# ESP32Programmer.net
KiCad netlist of a schematic drawn in Altium Designer
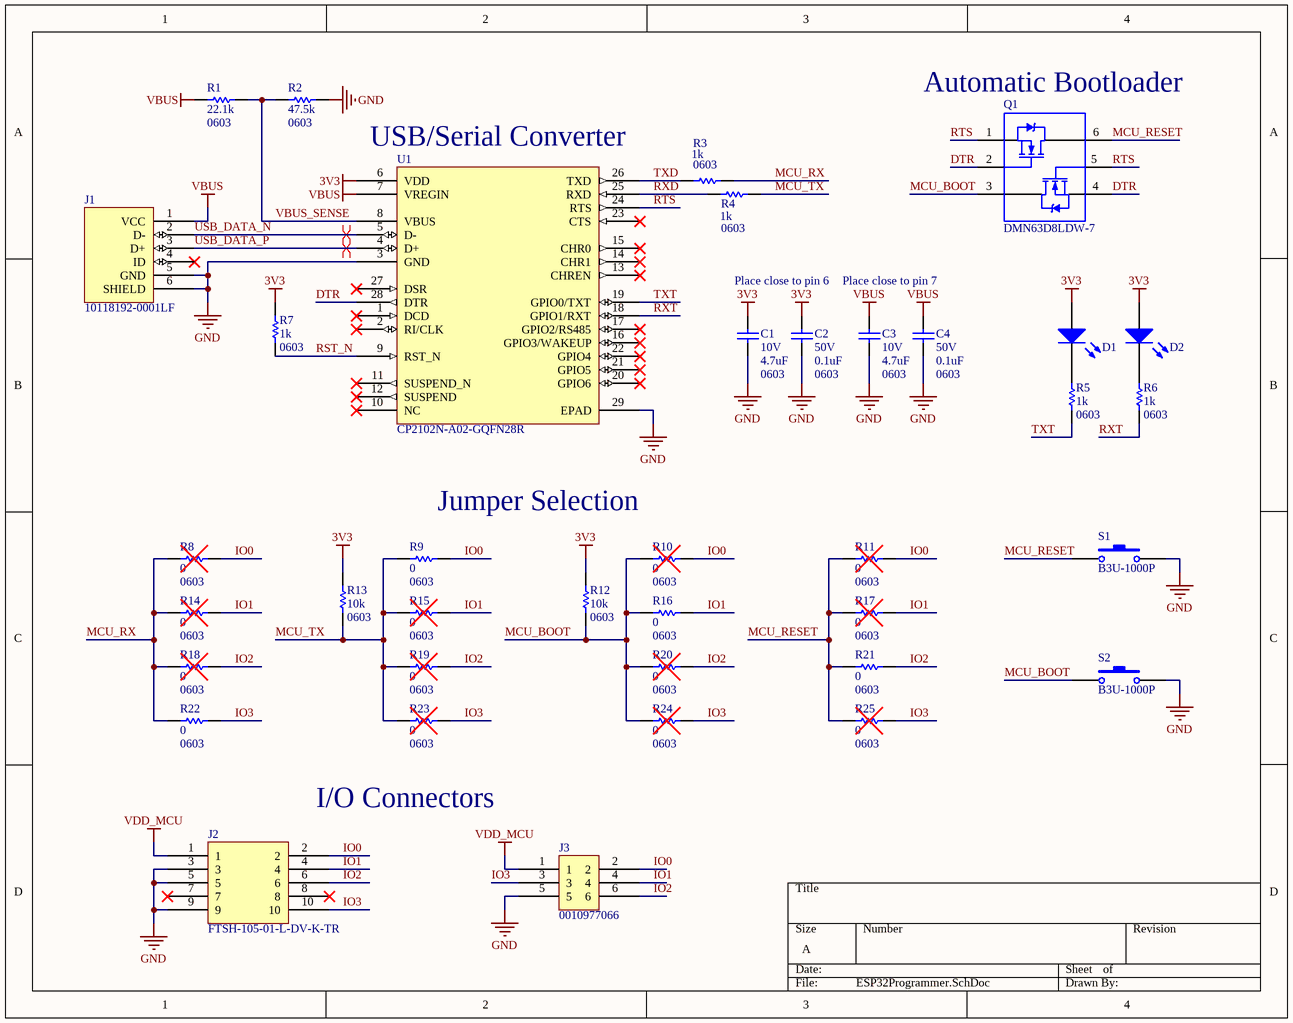
[diagram p0: ESP32Programmer.SchDoc]

(export (version "E")
  (design (tool "Eeschema 10.0.6"))
  (components
    (comp (ref "C1")
      (value "4.7uF")
      (footprint "Footprint_Capacitor:CAPC1608X09N")
      (description "General purpose capacitor")
      (fields
        (field (name "RATED VOLTAGE") "10V")
        (field (name "PACKAGE") "0603")
        (field (name "Comment") "Capacitor")
      )
      (libsource (lib "Schematic_Generic") (part "Capacitor"))
    )
    (comp (ref "C2")
      (value "0.1uF")
      (footprint "Footprint_Capacitor:CAPC1608X09N")
      (description "General purpose capacitor")
      (fields
        (field (name "RATED VOLTAGE") "50V")
        (field (name "PACKAGE") "0603")
        (field (name "Comment") "Capacitor")
      )
      (libsource (lib "Schematic_Generic") (part "Capacitor"))
    )
    (comp (ref "C3")
      (value "4.7uF")
      (footprint "Footprint_Capacitor:CAPC1608X09N")
      (description "General purpose capacitor")
      (fields
        (field (name "RATED VOLTAGE") "10V")
        (field (name "PACKAGE") "0603")
        (field (name "Comment") "Capacitor")
      )
      (libsource (lib "Schematic_Generic") (part "Capacitor"))
    )
    (comp (ref "C4")
      (value "0.1uF")
      (footprint "Footprint_Capacitor:CAPC1608X09N")
      (description "General purpose capacitor")
      (fields
        (field (name "RATED VOLTAGE") "50V")
        (field (name "PACKAGE") "0603")
        (field (name "Comment") "Capacitor")
      )
      (libsource (lib "Schematic_Generic") (part "Capacitor"))
    )
    (comp (ref "D1")
      (value "LED")
      (footprint "Footprint_LED:DIOC1608X09N")
      (description "General purpose LED")
      (libsource (lib "Schematic_Generic") (part "LED"))
    )
    (comp (ref "D2")
      (value "LED")
      (footprint "Footprint_LED:DIOC1608X09N")
      (description "General purpose LED")
      (libsource (lib "Schematic_Generic") (part "LED"))
    )
    (comp (ref "J1")
      (value "10118192-0001LF")
      (footprint "Footprint_Connector:10118192-0001LF")
      (description "Conn Micro USB 2.0 Type B RCP 5 POS 0.65mm Solder RA SMD 5 Terminal 1 Port T/R")
      (fields (field (name "MANUFACTURER") "Framatome Connectors"))
      (libsource (lib "Schematic_Connector") (part "10118192-0001LF"))
    )
    (comp (ref "J2")
      (value "FTSH-105-01-L-DV-K-TR")
      (footprint "Footprint_Connector:FTSH-105-01-L-DV-K-TR")
      (description "SAMTEC - FTSH-105-01-L-DV-K-TR - CONNECTOR, HEADER, 10 POSITION, 2ROW, 1.27MM")
      (fields (field (name "MANUFACTURER") "Samtec"))
      (libsource (lib "Schematic_Connector") (part "FTSH-105-01-L-DV-K-TR"))
    )
    (comp (ref "J3")
      (value "0010977066")
      (footprint "Footprint_Connector:3X2 MALE HEADER")
      (description "Conn Unshrouded Header HDR 6 POS 2.54mm Solder ST Thru-Hole C-GridR Bag")
      (fields (field (name "MANUFACTURER") "Molex"))
      (libsource (lib "Schematic_Connector") (part "0010977066"))
    )
    (comp (ref "Q1")
      (value "DMN63D8LDW-7")
      (footprint "Footprint_Transistor:SOT65P210X110-6N")
      (description "DIODES INC. - DMN63D8LDW-7 - Dual MOSFET, N Channel, 30 V, 260 mA, 2.8 ohm, SOT-363, Surface Mount")
      (fields (field (name "MANUFACTURER") "Diodes"))
      (libsource (lib "Schematic_Transistor") (part "DMN63D8LDW-7"))
    )
    (comp (ref "R1")
      (value "22.1k")
      (footprint "Footprint_Resistor:RESC1608X06N")
      (description "General purpose resistor")
      (fields (field (name "PACKAGE") "0603") (field (name "Comment") "Resistor"))
      (libsource (lib "Schematic_Generic") (part "Resistor"))
    )
    (comp (ref "R2")
      (value "47.5k")
      (footprint "Footprint_Resistor:RESC1608X06N")
      (description "General purpose resistor")
      (fields (field (name "PACKAGE") "0603") (field (name "Comment") "Resistor"))
      (libsource (lib "Schematic_Generic") (part "Resistor"))
    )
    (comp (ref "R3")
      (value "1k")
      (footprint "Footprint_Resistor:RESC1608X06N")
      (description "General purpose resistor")
      (fields (field (name "PACKAGE") "0603") (field (name "Comment") "Resistor"))
      (libsource (lib "Schematic_Generic") (part "Resistor"))
    )
    (comp (ref "R4")
      (value "1k")
      (footprint "Footprint_Resistor:RESC1608X06N")
      (description "General purpose resistor")
      (fields (field (name "PACKAGE") "0603") (field (name "Comment") "Resistor"))
      (libsource (lib "Schematic_Generic") (part "Resistor"))
    )
    (comp (ref "R5")
      (value "1k")
      (footprint "Footprint_Resistor:RESC1608X06N")
      (description "General purpose resistor")
      (fields (field (name "PACKAGE") "0603") (field (name "Comment") "Resistor"))
      (libsource (lib "Schematic_Generic") (part "Resistor"))
    )
    (comp (ref "R6")
      (value "1k")
      (footprint "Footprint_Resistor:RESC1608X06N")
      (description "General purpose resistor")
      (fields (field (name "PACKAGE") "0603") (field (name "Comment") "Resistor"))
      (libsource (lib "Schematic_Generic") (part "Resistor"))
    )
    (comp (ref "R7")
      (value "1k")
      (footprint "Footprint_Resistor:RESC1608X06N")
      (description "General purpose resistor")
      (fields (field (name "PACKAGE") "0603") (field (name "Comment") "Resistor"))
      (libsource (lib "Schematic_Generic") (part "Resistor"))
    )
    (comp (ref "R8")
      (value "0")
      (footprint "Footprint_Resistor:RESC1608X06N")
      (description "General purpose resistor")
      (fields (field (name "PACKAGE") "0603") (field (name "Comment") "Resistor"))
      (libsource (lib "Schematic_Generic") (part "Resistor"))
    )
    (comp (ref "R9")
      (value "0")
      (footprint "Footprint_Resistor:RESC1608X06N")
      (description "General purpose resistor")
      (fields (field (name "PACKAGE") "0603") (field (name "Comment") "Resistor"))
      (libsource (lib "Schematic_Generic") (part "Resistor"))
    )
    (comp (ref "R10")
      (value "0")
      (footprint "Footprint_Resistor:RESC1608X06N")
      (description "General purpose resistor")
      (fields (field (name "PACKAGE") "0603") (field (name "Comment") "Resistor"))
      (libsource (lib "Schematic_Generic") (part "Resistor"))
    )
    (comp (ref "R11")
      (value "0")
      (footprint "Footprint_Resistor:RESC1608X06N")
      (description "General purpose resistor")
      (fields (field (name "PACKAGE") "0603") (field (name "Comment") "Resistor"))
      (libsource (lib "Schematic_Generic") (part "Resistor"))
    )
    (comp (ref "R12")
      (value "10k")
      (footprint "Footprint_Resistor:RESC1608X06N")
      (description "General purpose resistor")
      (fields (field (name "PACKAGE") "0603") (field (name "Comment") "Resistor"))
      (libsource (lib "Schematic_Generic") (part "Resistor"))
    )
    (comp (ref "R13")
      (value "10k")
      (footprint "Footprint_Resistor:RESC1608X06N")
      (description "General purpose resistor")
      (fields (field (name "PACKAGE") "0603") (field (name "Comment") "Resistor"))
      (libsource (lib "Schematic_Generic") (part "Resistor"))
    )
    (comp (ref "R14")
      (value "0")
      (footprint "Footprint_Resistor:RESC1608X06N")
      (description "General purpose resistor")
      (fields (field (name "PACKAGE") "0603") (field (name "Comment") "Resistor"))
      (libsource (lib "Schematic_Generic") (part "Resistor"))
    )
    (comp (ref "R15")
      (value "0")
      (footprint "Footprint_Resistor:RESC1608X06N")
      (description "General purpose resistor")
      (fields (field (name "PACKAGE") "0603") (field (name "Comment") "Resistor"))
      (libsource (lib "Schematic_Generic") (part "Resistor"))
    )
    (comp (ref "R16")
      (value "0")
      (footprint "Footprint_Resistor:RESC1608X06N")
      (description "General purpose resistor")
      (fields (field (name "PACKAGE") "0603") (field (name "Comment") "Resistor"))
      (libsource (lib "Schematic_Generic") (part "Resistor"))
    )
    (comp (ref "R17")
      (value "0")
      (footprint "Footprint_Resistor:RESC1608X06N")
      (description "General purpose resistor")
      (fields (field (name "PACKAGE") "0603") (field (name "Comment") "Resistor"))
      (libsource (lib "Schematic_Generic") (part "Resistor"))
    )
    (comp (ref "R18")
      (value "0")
      (footprint "Footprint_Resistor:RESC1608X06N")
      (description "General purpose resistor")
      (fields (field (name "PACKAGE") "0603") (field (name "Comment") "Resistor"))
      (libsource (lib "Schematic_Generic") (part "Resistor"))
    )
    (comp (ref "R19")
      (value "0")
      (footprint "Footprint_Resistor:RESC1608X06N")
      (description "General purpose resistor")
      (fields (field (name "PACKAGE") "0603") (field (name "Comment") "Resistor"))
      (libsource (lib "Schematic_Generic") (part "Resistor"))
    )
    (comp (ref "R20")
      (value "0")
      (footprint "Footprint_Resistor:RESC1608X06N")
      (description "General purpose resistor")
      (fields (field (name "PACKAGE") "0603") (field (name "Comment") "Resistor"))
      (libsource (lib "Schematic_Generic") (part "Resistor"))
    )
    (comp (ref "R21")
      (value "0")
      (footprint "Footprint_Resistor:RESC1608X06N")
      (description "General purpose resistor")
      (fields (field (name "PACKAGE") "0603") (field (name "Comment") "Resistor"))
      (libsource (lib "Schematic_Generic") (part "Resistor"))
    )
    (comp (ref "R22")
      (value "0")
      (footprint "Footprint_Resistor:RESC1608X06N")
      (description "General purpose resistor")
      (fields (field (name "PACKAGE") "0603") (field (name "Comment") "Resistor"))
      (libsource (lib "Schematic_Generic") (part "Resistor"))
    )
    (comp (ref "R23")
      (value "0")
      (footprint "Footprint_Resistor:RESC1608X06N")
      (description "General purpose resistor")
      (fields (field (name "PACKAGE") "0603") (field (name "Comment") "Resistor"))
      (libsource (lib "Schematic_Generic") (part "Resistor"))
    )
    (comp (ref "R24")
      (value "0")
      (footprint "Footprint_Resistor:RESC1608X06N")
      (description "General purpose resistor")
      (fields (field (name "PACKAGE") "0603") (field (name "Comment") "Resistor"))
      (libsource (lib "Schematic_Generic") (part "Resistor"))
    )
    (comp (ref "R25")
      (value "0")
      (footprint "Footprint_Resistor:RESC1608X06N")
      (description "General purpose resistor")
      (fields (field (name "PACKAGE") "0603") (field (name "Comment") "Resistor"))
      (libsource (lib "Schematic_Generic") (part "Resistor"))
    )
    (comp (ref "S1")
      (value "B3U-1000P")
      (footprint "Footprint_Button:B3U-1000P")
      (description "OMRON ELECTRONIC COMPONENTS         B3U-1000P            SWITCH, SPST-NO, 0.05A, 12V, SMD")
      (fields (field (name "MANUFACTURER") "Omron"))
      (libsource (lib "Schematic_Button") (part "B3U-1000P"))
    )
    (comp (ref "S2")
      (value "B3U-1000P")
      (footprint "Footprint_Button:B3U-1000P")
      (description "OMRON ELECTRONIC COMPONENTS         B3U-1000P            SWITCH, SPST-NO, 0.05A, 12V, SMD")
      (fields (field (name "MANUFACTURER") "Omron"))
      (libsource (lib "Schematic_Button") (part "B3U-1000P"))
    )
    (comp (ref "U1")
      (value "CP2102N-A02-GQFN28R")
      (footprint "Footprint_IC:QFN50P500X500X80_HS-29N")
      (description "Full Speed USB to UART Bridge USB 2.0 3.3V T/R Automotive 28-Pin QFN EP")
      (fields (field (name "MANUFACTURER") "Silicon Labs"))
      (libsource (lib "Schematic_IC") (part "CP2102N-A02-GQFN28R"))
    )
  )
  (nets
    (net (code "1") (name "/DTR") (class "Default")
      (node (ref "Q1") (pin "2") (pinfunction "G1_2") (pintype "passive"))
      (node (ref "Q1") (pin "4") (pinfunction "S2_4") (pintype "passive"))
      (node (ref "U1") (pin "28") (pinfunction "DTR_28") (pintype "output"))
    )
    (net (code "2") (name "/IO0") (class "Default")
      (node (ref "J2") (pin "2") (pinfunction "2_2") (pintype "passive"))
      (node (ref "J3") (pin "2") (pinfunction "2_2") (pintype "passive"))
      (node (ref "R10") (pin "2") (pinfunction "2_2") (pintype "passive"))
      (node (ref "R11") (pin "2") (pinfunction "2_2") (pintype "passive"))
      (node (ref "R8") (pin "2") (pinfunction "2_2") (pintype "passive"))
      (node (ref "R9") (pin "2") (pinfunction "2_2") (pintype "passive"))
    )
    (net (code "3") (name "/IO1") (class "Default")
      (node (ref "J2") (pin "4") (pinfunction "4_4") (pintype "passive"))
      (node (ref "J3") (pin "4") (pinfunction "4_4") (pintype "passive"))
      (node (ref "R14") (pin "2") (pinfunction "2_2") (pintype "passive"))
      (node (ref "R15") (pin "2") (pinfunction "2_2") (pintype "passive"))
      (node (ref "R16") (pin "2") (pinfunction "2_2") (pintype "passive"))
      (node (ref "R17") (pin "2") (pinfunction "2_2") (pintype "passive"))
    )
    (net (code "4") (name "/IO2") (class "Default")
      (node (ref "J2") (pin "6") (pinfunction "6_6") (pintype "passive"))
      (node (ref "J3") (pin "6") (pinfunction "6_6") (pintype "passive"))
      (node (ref "R18") (pin "2") (pinfunction "2_2") (pintype "passive"))
      (node (ref "R19") (pin "2") (pinfunction "2_2") (pintype "passive"))
      (node (ref "R20") (pin "2") (pinfunction "2_2") (pintype "passive"))
      (node (ref "R21") (pin "2") (pinfunction "2_2") (pintype "passive"))
    )
    (net (code "5") (name "/IO3") (class "Default")
      (node (ref "J2") (pin "10") (pinfunction "10_10") (pintype "passive"))
      (node (ref "J3") (pin "3") (pinfunction "3_3") (pintype "passive"))
      (node (ref "R22") (pin "2") (pinfunction "2_2") (pintype "passive"))
      (node (ref "R23") (pin "2") (pinfunction "2_2") (pintype "passive"))
      (node (ref "R24") (pin "2") (pinfunction "2_2") (pintype "passive"))
      (node (ref "R25") (pin "2") (pinfunction "2_2") (pintype "passive"))
    )
    (net (code "6") (name "/MCU_BOOT") (class "Default")
      (node (ref "Q1") (pin "3") (pinfunction "D2_3") (pintype "passive"))
      (node (ref "R10") (pin "1") (pinfunction "1_1") (pintype "passive"))
      (node (ref "R12") (pin "2") (pinfunction "2_2") (pintype "passive"))
      (node (ref "R16") (pin "1") (pinfunction "1_1") (pintype "passive"))
      (node (ref "R20") (pin "1") (pinfunction "1_1") (pintype "passive"))
      (node (ref "R24") (pin "1") (pinfunction "1_1") (pintype "passive"))
      (node (ref "S2") (pin "1") (pinfunction "1_1") (pintype "passive"))
    )
    (net (code "7") (name "/MCU_RESET") (class "Default")
      (node (ref "Q1") (pin "6") (pinfunction "D1_6") (pintype "passive"))
      (node (ref "R11") (pin "1") (pinfunction "1_1") (pintype "passive"))
      (node (ref "R17") (pin "1") (pinfunction "1_1") (pintype "passive"))
      (node (ref "R21") (pin "1") (pinfunction "1_1") (pintype "passive"))
      (node (ref "R25") (pin "1") (pinfunction "1_1") (pintype "passive"))
      (node (ref "S1") (pin "1") (pinfunction "1_1") (pintype "passive"))
    )
    (net (code "8") (name "/MCU_RX") (class "Default")
      (node (ref "R14") (pin "1") (pinfunction "1_1") (pintype "passive"))
      (node (ref "R18") (pin "1") (pinfunction "1_1") (pintype "passive"))
      (node (ref "R22") (pin "1") (pinfunction "1_1") (pintype "passive"))
      (node (ref "R3") (pin "1") (pinfunction "1_1") (pintype "passive"))
      (node (ref "R8") (pin "1") (pinfunction "1_1") (pintype "passive"))
    )
    (net (code "9") (name "/MCU_TX") (class "Default")
      (node (ref "R13") (pin "2") (pinfunction "2_2") (pintype "passive"))
      (node (ref "R15") (pin "1") (pinfunction "1_1") (pintype "passive"))
      (node (ref "R19") (pin "1") (pinfunction "1_1") (pintype "passive"))
      (node (ref "R23") (pin "1") (pinfunction "1_1") (pintype "passive"))
      (node (ref "R4") (pin "1") (pinfunction "1_1") (pintype "passive"))
      (node (ref "R9") (pin "1") (pinfunction "1_1") (pintype "passive"))
    )
    (net (code "10") (name "/RST_N") (class "Default")
      (node (ref "R7") (pin "2") (pinfunction "2_2") (pintype "passive"))
      (node (ref "U1") (pin "9") (pinfunction "RST_N_9") (pintype "input"))
    )
    (net (code "11") (name "/RTS") (class "Default")
      (node (ref "Q1") (pin "1") (pinfunction "S1_1") (pintype "passive"))
      (node (ref "Q1") (pin "5") (pinfunction "G2_5") (pintype "passive"))
      (node (ref "U1") (pin "24") (pinfunction "RTS_24") (pintype "output"))
    )
    (net (code "12") (name "/RXD") (class "Default")
      (node (ref "R4") (pin "2") (pinfunction "2_2") (pintype "passive"))
      (node (ref "U1") (pin "25") (pinfunction "RXD_25") (pintype "input"))
    )
    (net (code "13") (name "/RXT") (class "Default")
      (node (ref "R6") (pin "2") (pinfunction "2_2") (pintype "passive"))
      (node (ref "U1") (pin "18") (pinfunction "GPIO1/RXT_18") (pintype "bidirectional"))
    )
    (net (code "14") (name "/TXD") (class "Default")
      (node (ref "R3") (pin "2") (pinfunction "2_2") (pintype "passive"))
      (node (ref "U1") (pin "26") (pinfunction "TXD_26") (pintype "output"))
    )
    (net (code "15") (name "/TXT") (class "Default")
      (node (ref "R5") (pin "2") (pinfunction "2_2") (pintype "passive"))
      (node (ref "U1") (pin "19") (pinfunction "GPIO0/TXT_19") (pintype "bidirectional"))
    )
    (net (code "16") (name "/USB_DATA_N") (class "Default")
      (node (ref "J1") (pin "2") (pinfunction "D-_2") (pintype "bidirectional"))
      (node (ref "U1") (pin "5") (pinfunction "D-_5") (pintype "bidirectional"))
    )
    (net (code "17") (name "/USB_DATA_P") (class "Default")
      (node (ref "J1") (pin "3") (pinfunction "D+_3") (pintype "bidirectional"))
      (node (ref "U1") (pin "4") (pinfunction "D+_4") (pintype "bidirectional"))
    )
    (net (code "18") (name "/VBUS_SENSE") (class "Default")
      (node (ref "R1") (pin "2") (pinfunction "2_2") (pintype "passive"))
      (node (ref "R2") (pin "1") (pinfunction "1_1") (pintype "passive"))
      (node (ref "U1") (pin "8") (pinfunction "VBUS_8") (pintype "power_in"))
    )
    (net (code "19") (name "3V3") (class "Default")
      (node (ref "C1") (pin "2") (pinfunction "2_2") (pintype "passive"))
      (node (ref "C2") (pin "2") (pinfunction "2_2") (pintype "passive"))
      (node (ref "D1") (pin "1") (pinfunction "A_1") (pintype "passive"))
      (node (ref "D2") (pin "1") (pinfunction "A_1") (pintype "passive"))
      (node (ref "R12") (pin "1") (pinfunction "1_1") (pintype "passive"))
      (node (ref "R13") (pin "1") (pinfunction "1_1") (pintype "passive"))
      (node (ref "R7") (pin "1") (pinfunction "1_1") (pintype "passive"))
      (node (ref "U1") (pin "6") (pinfunction "VDD_6") (pintype "power_in"))
    )
    (net (code "20") (name "GND") (class "Default")
      (node (ref "C1") (pin "1") (pinfunction "1_1") (pintype "passive"))
      (node (ref "C2") (pin "1") (pinfunction "1_1") (pintype "passive"))
      (node (ref "C3") (pin "1") (pinfunction "1_1") (pintype "passive"))
      (node (ref "C4") (pin "1") (pinfunction "1_1") (pintype "passive"))
      (node (ref "J1") (pin "5") (pinfunction "GND_5") (pintype "power_in"))
      (node (ref "J1") (pin "6") (pinfunction "SHIELD_6") (pintype "passive"))
      (node (ref "J2") (pin "3") (pinfunction "3_3") (pintype "passive"))
      (node (ref "J2") (pin "5") (pinfunction "5_5") (pintype "passive"))
      (node (ref "J2") (pin "9") (pinfunction "9_9") (pintype "passive"))
      (node (ref "J3") (pin "5") (pinfunction "5_5") (pintype "passive"))
      (node (ref "R2") (pin "2") (pinfunction "2_2") (pintype "passive"))
      (node (ref "S1") (pin "2") (pinfunction "2_2") (pintype "passive"))
      (node (ref "S2") (pin "2") (pinfunction "2_2") (pintype "passive"))
      (node (ref "U1") (pin "29") (pinfunction "EPAD_29") (pintype "power_in"))
      (node (ref "U1") (pin "3") (pinfunction "GND_3") (pintype "power_in"))
    )
    (net (code "21") (name "Net-(D1-K)") (class "Default")
      (node (ref "D1") (pin "2") (pinfunction "K_2") (pintype "passive"))
      (node (ref "R5") (pin "1") (pinfunction "1_1") (pintype "passive"))
    )
    (net (code "22") (name "Net-(D2-K)") (class "Default")
      (node (ref "D2") (pin "2") (pinfunction "K_2") (pintype "passive"))
      (node (ref "R6") (pin "1") (pinfunction "1_1") (pintype "passive"))
    )
    (net (code "23") (name "VBUS") (class "Default")
      (node (ref "C3") (pin "2") (pinfunction "2_2") (pintype "passive"))
      (node (ref "C4") (pin "2") (pinfunction "2_2") (pintype "passive"))
      (node (ref "J1") (pin "1") (pinfunction "VCC_1") (pintype "power_in"))
      (node (ref "R1") (pin "1") (pinfunction "1_1") (pintype "passive"))
      (node (ref "U1") (pin "7") (pinfunction "VREGIN_7") (pintype "power_in"))
    )
    (net (code "24") (name "VDD_MCU") (class "Default")
      (node (ref "J2") (pin "1") (pinfunction "1_1") (pintype "passive"))
      (node (ref "J3") (pin "1") (pinfunction "1_1") (pintype "passive"))
    )
    (net (code "25") (name "unconnected-(J1-ID-Pad4)") (class "Default")
      (node (ref "J1") (pin "4") (pinfunction "ID_4") (pintype "bidirectional+no_connect"))
    )
    (net (code "26") (name "unconnected-(J2-Pad7)") (class "Default")
      (node (ref "J2") (pin "7") (pinfunction "7_7") (pintype "passive+no_connect"))
    )
    (net (code "27") (name "unconnected-(J2-Pad8)") (class "Default")
      (node (ref "J2") (pin "8") (pinfunction "8_8") (pintype "passive+no_connect"))
    )
    (net (code "28") (name "unconnected-(U1-CHR0-Pad15)") (class "Default")
      (node (ref "U1") (pin "15") (pinfunction "CHR0_15") (pintype "output+no_connect"))
    )
    (net (code "29") (name "unconnected-(U1-CHR1-Pad14)") (class "Default")
      (node (ref "U1") (pin "14") (pinfunction "CHR1_14") (pintype "output+no_connect"))
    )
    (net (code "30") (name "unconnected-(U1-CHREN-Pad13)") (class "Default")
      (node (ref "U1") (pin "13") (pinfunction "CHREN_13") (pintype "output+no_connect"))
    )
    (net (code "31") (name "unconnected-(U1-CTS-Pad23)") (class "Default")
      (node (ref "U1") (pin "23") (pinfunction "CTS_23") (pintype "input+no_connect"))
    )
    (net (code "32") (name "unconnected-(U1-DCD-Pad1)") (class "Default")
      (node (ref "U1") (pin "1") (pinfunction "DCD_1") (pintype "input+no_connect"))
    )
    (net (code "33") (name "unconnected-(U1-DSR-Pad27)") (class "Default")
      (node (ref "U1") (pin "27") (pinfunction "DSR_27") (pintype "input+no_connect"))
    )
    (net (code "34") (name "unconnected-(U1-GPIO2{slash}RS485-Pad17)") (class "Default")
      (node (ref "U1") (pin "17") (pinfunction "GPIO2/RS485_17") (pintype "bidirectional+no_connect"))
    )
    (net (code "35") (name "unconnected-(U1-GPIO3{slash}WAKEUP-Pad16)") (class "Default")
      (node (ref "U1") (pin "16") (pinfunction "GPIO3/WAKEUP_16") (pintype "bidirectional+no_connect"))
    )
    (net (code "36") (name "unconnected-(U1-GPIO4-Pad22)") (class "Default")
      (node (ref "U1") (pin "22") (pinfunction "GPIO4_22") (pintype "bidirectional+no_connect"))
    )
    (net (code "37") (name "unconnected-(U1-GPIO5-Pad21)") (class "Default")
      (node (ref "U1") (pin "21") (pinfunction "GPIO5_21") (pintype "bidirectional+no_connect"))
    )
    (net (code "38") (name "unconnected-(U1-GPIO6-Pad20)") (class "Default")
      (node (ref "U1") (pin "20") (pinfunction "GPIO6_20") (pintype "bidirectional+no_connect"))
    )
    (net (code "39") (name "unconnected-(U1-NC-Pad10)") (class "Default")
      (node (ref "U1") (pin "10") (pinfunction "NC_10") (pintype "passive+no_connect"))
    )
    (net (code "40") (name "unconnected-(U1-RI{slash}CLK-Pad2)") (class "Default")
      (node (ref "U1") (pin "2") (pinfunction "RI/CLK_2") (pintype "bidirectional+no_connect"))
    )
    (net (code "41") (name "unconnected-(U1-SUSPEND-Pad12)") (class "Default")
      (node (ref "U1") (pin "12") (pinfunction "SUSPEND_12") (pintype "output+no_connect"))
    )
    (net (code "42") (name "unconnected-(U1-SUSPEND_N-Pad11)") (class "Default")
      (node (ref "U1") (pin "11") (pinfunction "SUSPEND_N_11") (pintype "output+no_connect"))
    )
  )
)
